# MCU.net
KiCad netlist of a schematic drawn in Altium Designer
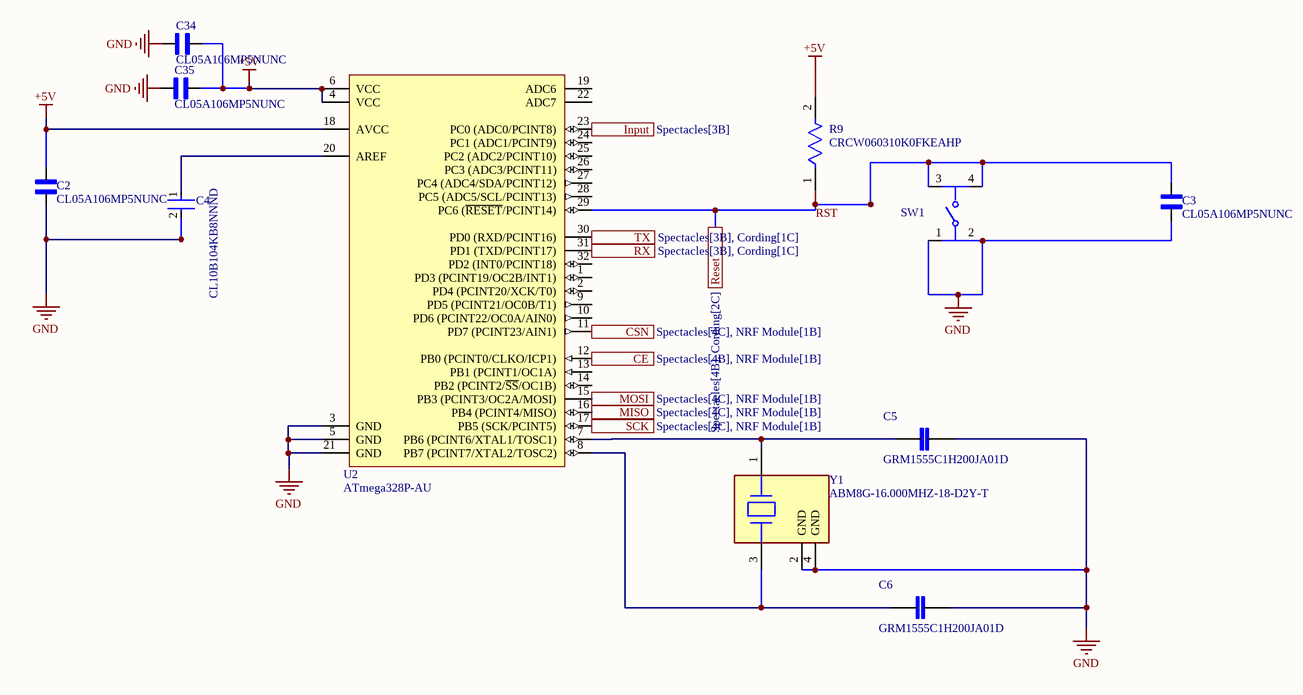
[diagram p0: MCU.SchDoc]

(export (version "E")
  (design (tool "Eeschema 10.0.6"))
  (components
    (comp (ref "C2")
      (value "CL05A106MP5NUNC")
      (footprint "CAPC1005X55N")
      (description "10 ÂµF Â±20% 10V Ceramic Capacitor X5R 0402 (1005 Metric)")
      (fields
        (field (name "OCTOPART") "https://octopart.com/grm188r61a106ke69d-murata-22851381")
        (field (name "MANUFACTURER PART NUMBER") "GRM188R61A106KE69D")
      )
      (libsource (lib "") (part "CL05A106MP5NUNC_1"))
    )
    (comp (ref "C3")
      (value "CL05A106MP5NUNC")
      (footprint "CAPC1005X55N")
      (description "10 ÂµF Â±20% 10V Ceramic Capacitor X5R 0402 (1005 Metric)")
      (fields
        (field (name "OCTOPART") "https://octopart.com/grm188r61a106ke69d-murata-22851381")
        (field (name "MANUFACTURER PART NUMBER") "GRM188R61A106KE69D")
      )
      (libsource (lib "") (part "CL05A106MP5NUNC_1"))
    )
    (comp (ref "C4")
      (value "CL10B104KB8NNND")
      (footprint "FP-CL10-IPC_A")
      (description "Cap Ceramic 100nF 50V X7R ±10% Pad SMD 0603 +125°C T/R")
      (fields (field (name "VOLTAGE") "50V") (field (name "TOLERANCE") "10%"))
      (libsource (lib "Altium Content Vault") (part "b4654b650e69147ec39a6b967a45e02"))
    )
    (comp (ref "C5")
      (value "GRM1555C1H200JA01D")
      (footprint "CAPC1005X55N")
      (description "SMD Capacitor C0G(EIA) with Capacitance: 20pF Tol. 5%. Rated Voltage: 50Vdc")
      (fields (field (name "MF") "Murata"))
      (libsource (lib "GRM1555C1H200JA01D") (part "GRM1555C1H200JA01D"))
    )
    (comp (ref "C6")
      (value "GRM1555C1H200JA01D")
      (footprint "CAPC1005X55N")
      (description "SMD Capacitor C0G(EIA) with Capacitance: 20pF Tol. 5%. Rated Voltage: 50Vdc")
      (fields (field (name "MF") "Murata"))
      (libsource (lib "GRM1555C1H200JA01D") (part "GRM1555C1H200JA01D"))
    )
    (comp (ref "C34")
      (value "CL05A106MP5NUNC")
      (footprint "CAPC1005X55N")
      (description "10 ÂµF Â±20% 10V Ceramic Capacitor X5R 0402 (1005 Metric)")
      (fields
        (field (name "OCTOPART") "https://octopart.com/grm188r61a106ke69d-murata-22851381")
        (field (name "MANUFACTURER PART NUMBER") "GRM188R61A106KE69D")
      )
      (libsource (lib "CL05A106MP5NUNC") (part "CL05A106MP5NUNC"))
    )
    (comp (ref "C35")
      (value "CL05A106MP5NUNC")
      (footprint "CAPC1005X55N")
      (description "10 ÂµF Â±20% 10V Ceramic Capacitor X5R 0402 (1005 Metric)")
      (fields
        (field (name "OCTOPART") "https://octopart.com/grm188r61a106ke69d-murata-22851381")
        (field (name "MANUFACTURER PART NUMBER") "GRM188R61A106KE69D")
      )
      (libsource (lib "CL05A106MP5NUNC") (part "CL05A106MP5NUNC"))
    )
    (comp (ref "R9")
      (value "CRCW060310K0FKEAHP")
      (footprint "FP-CRCW0603-HPe3-MFG")
      (description "RES SMD 10K OHM 1% 1/3W 0603")
      (fields (field (name "TOLERANCE") "1%"))
      (libsource (lib "Altium Content Vault") (part "1029c3af85768c4190bb7ad29bc67b5"))
    )
    (comp (ref "SW1")
      (value "PTS526SK15SMTR2LFS")
      (footprint "FP-PTS526SK15SMTR2LFS-MFG")
      (description "TACT 5.2 X 5.2, 1.5 MM H, 260GF,")
      (fields
        (field (name "MANUFACTURER") "C&K")
        (field (name "OCTOPART") "https://octopart.com/pts526+sk15+smtr2+lfs-c%26k+components-100617999")
      )
      (libsource (lib "Altium Content Vault") (part "b8895f3f4cefb76e1819d2863dba89b"))
    )
    (comp (ref "U2")
      (value "ATmega328P-AU")
      (footprint "32A_M")
      (libsource (lib "Altium Content Vault") (part "MC-8B-ATM48-SQ32"))
    )
    (comp (ref "Y1")
      (value "ABM8G-16.000MHZ-18-D2Y-T")
      (footprint "FP-ABM8G-MFG")
      (description "Crystal 12MHz ±20ppm (Tol) ±30ppm (Stability) 18pF FUND 120Ω 4-Pin SMD T/R")
      (fields (field (name "TOLERANCE") "20ppm"))
      (libsource (lib "Altium Content Vault") (part "48e526d86b7f2615d98721063c72f49"))
    )
  )
  (nets
    (net (code "1") (name "+5V") (class "Default")
      (node (ref "C2") (pin "2") (pinfunction "2_2") (pintype "passive"))
      (node (ref "C34") (pin "1") (pinfunction "1_1") (pintype "passive"))
      (node (ref "C35") (pin "1") (pinfunction "1_1") (pintype "passive"))
      (node (ref "R9") (pin "2") (pinfunction "2_2") (pintype "passive"))
      (node (ref "U2") (pin "18") (pinfunction "AVCC_18") (pintype "power_in"))
      (node (ref "U2") (pin "4") (pinfunction "VCC_4") (pintype "power_in"))
      (node (ref "U2") (pin "6") (pinfunction "VCC_6") (pintype "power_in"))
    )
    (net (code "2") (name "/CE") (class "Default")
      (node (ref "U2") (pin "12") (pinfunction "PB0_(PCINT0/CLKO/ICP1)_12") (pintype "input"))
    )
    (net (code "3") (name "/CSN") (class "Default")
      (node (ref "U2") (pin "11") (pinfunction "PD7_(PCINT23/AIN1)_11") (pintype "output"))
    )
    (net (code "4") (name "/Input") (class "Default")
      (node (ref "U2") (pin "23") (pinfunction "PC0_(ADC0/PCINT8)_23") (pintype "bidirectional"))
    )
    (net (code "5") (name "/MISO") (class "Default")
      (node (ref "U2") (pin "16") (pinfunction "PB4_(PCINT4/MISO)_16") (pintype "bidirectional"))
    )
    (net (code "6") (name "/MOSI") (class "Default")
      (node (ref "U2") (pin "15") (pinfunction "PB3_(PCINT3/OC2A/MOSI)_15") (pintype "passive"))
    )
    (net (code "7") (name "/RST") (class "Default")
      (node (ref "C3") (pin "2") (pinfunction "2_2") (pintype "passive"))
      (node (ref "R9") (pin "1") (pinfunction "1_1") (pintype "passive"))
      (node (ref "SW1") (pin "3") (pinfunction "3_3") (pintype "passive"))
      (node (ref "SW1") (pin "4") (pinfunction "4_4") (pintype "passive"))
      (node (ref "U2") (pin "29") (pinfunction "PC6_(~{RESET}/PCINT14)_29") (pintype "bidirectional"))
    )
    (net (code "8") (name "/RX") (class "Default")
      (node (ref "U2") (pin "31") (pinfunction "PD1_(TXD/PCINT17)_31") (pintype "passive"))
    )
    (net (code "9") (name "/SCK") (class "Default")
      (node (ref "U2") (pin "17") (pinfunction "PB5_(SCK/PCINT5)_17") (pintype "bidirectional"))
    )
    (net (code "10") (name "/TX") (class "Default")
      (node (ref "U2") (pin "30") (pinfunction "PD0_(RXD/PCINT16)_30") (pintype "passive"))
    )
    (net (code "11") (name "GND") (class "Default")
      (node (ref "C2") (pin "1") (pinfunction "1_1") (pintype "passive"))
      (node (ref "C3") (pin "1") (pinfunction "1_1") (pintype "passive"))
      (node (ref "C34") (pin "2") (pinfunction "2_2") (pintype "passive"))
      (node (ref "C35") (pin "2") (pinfunction "2_2") (pintype "passive"))
      (node (ref "C4") (pin "2") (pinfunction "2_2") (pintype "passive"))
      (node (ref "C5") (pin "1") (pinfunction "1_1") (pintype "passive"))
      (node (ref "C6") (pin "1") (pinfunction "1_1") (pintype "passive"))
      (node (ref "SW1") (pin "1") (pinfunction "1_1") (pintype "passive"))
      (node (ref "SW1") (pin "2") (pinfunction "2_2") (pintype "passive"))
      (node (ref "U2") (pin "21") (pinfunction "GND_21") (pintype "power_in"))
      (node (ref "U2") (pin "3") (pinfunction "GND_3") (pintype "power_in"))
      (node (ref "U2") (pin "5") (pinfunction "GND_5") (pintype "power_in"))
      (node (ref "Y1") (pin "2") (pinfunction "GND_2") (pintype "power_in"))
      (node (ref "Y1") (pin "4") (pinfunction "GND_4") (pintype "power_in"))
    )
    (net (code "12") (name "Net-(U2-AREF)") (class "Default")
      (node (ref "C4") (pin "1") (pinfunction "1_1") (pintype "passive"))
      (node (ref "U2") (pin "20") (pinfunction "AREF_20") (pintype "passive"))
    )
    (net (code "13") (name "Net-(U2-PB6_(PCINT6{slash}XTAL1{slash}TOSC1))") (class "Default")
      (node (ref "C5") (pin "2") (pinfunction "2_2") (pintype "passive"))
      (node (ref "U2") (pin "7") (pinfunction "PB6_(PCINT6/XTAL1/TOSC1)_7") (pintype "bidirectional"))
      (node (ref "Y1") (pin "1") (pinfunction "1_1") (pintype "passive"))
    )
    (net (code "14") (name "Net-(U2-PB7_(PCINT7{slash}XTAL2{slash}TOSC2))") (class "Default")
      (node (ref "C6") (pin "2") (pinfunction "2_2") (pintype "passive"))
      (node (ref "U2") (pin "8") (pinfunction "PB7_(PCINT7/XTAL2/TOSC2)_8") (pintype "bidirectional"))
      (node (ref "Y1") (pin "3") (pinfunction "3_3") (pintype "passive"))
    )
    (net (code "15") (name "unconnected-(U2-ADC6-Pad19)") (class "Default")
      (node (ref "U2") (pin "19") (pinfunction "ADC6_19") (pintype "passive"))
    )
    (net (code "16") (name "unconnected-(U2-ADC7-Pad22)") (class "Default")
      (node (ref "U2") (pin "22") (pinfunction "ADC7_22") (pintype "passive"))
    )
    (net (code "17") (name "unconnected-(U2-PB1_(PCINT1{slash}OC1A)-Pad13)") (class "Default")
      (node (ref "U2") (pin "13") (pinfunction "PB1_(PCINT1/OC1A)_13") (pintype "input"))
    )
    (net (code "18") (name "unconnected-(U2-PB2_(PCINT2{slash}~{SS}{slash}OC1B)-Pad14)") (class "Default")
      (node (ref "U2") (pin "14") (pinfunction "PB2_(PCINT2/~{SS}/OC1B)_14") (pintype "bidirectional"))
    )
    (net (code "19") (name "unconnected-(U2-PC1_(ADC1{slash}PCINT9)-Pad24)") (class "Default")
      (node (ref "U2") (pin "24") (pinfunction "PC1_(ADC1/PCINT9)_24") (pintype "bidirectional"))
    )
    (net (code "20") (name "unconnected-(U2-PC2_(ADC2{slash}PCINT10)-Pad25)") (class "Default")
      (node (ref "U2") (pin "25") (pinfunction "PC2_(ADC2/PCINT10)_25") (pintype "bidirectional"))
    )
    (net (code "21") (name "unconnected-(U2-PC3_(ADC3{slash}PCINT11)-Pad26)") (class "Default")
      (node (ref "U2") (pin "26") (pinfunction "PC3_(ADC3/PCINT11)_26") (pintype "bidirectional"))
    )
    (net (code "22") (name "unconnected-(U2-PC4_(ADC4{slash}SDA{slash}PCINT12)-Pad27)") (class "Default")
      (node (ref "U2") (pin "27") (pinfunction "PC4_(ADC4/SDA/PCINT12)_27") (pintype "output"))
    )
    (net (code "23") (name "unconnected-(U2-PC5_(ADC5{slash}SCL{slash}PCINT13)-Pad28)") (class "Default")
      (node (ref "U2") (pin "28") (pinfunction "PC5_(ADC5/SCL/PCINT13)_28") (pintype "output"))
    )
    (net (code "24") (name "unconnected-(U2-PD2_(INT0{slash}PCINT18)-Pad32)") (class "Default")
      (node (ref "U2") (pin "32") (pinfunction "PD2_(INT0/PCINT18)_32") (pintype "bidirectional"))
    )
    (net (code "25") (name "unconnected-(U2-PD3_(PCINT19{slash}OC2B{slash}INT1)-Pad1)") (class "Default")
      (node (ref "U2") (pin "1") (pinfunction "PD3_(PCINT19/OC2B/INT1)_1") (pintype "bidirectional"))
    )
    (net (code "26") (name "unconnected-(U2-PD4_(PCINT20{slash}XCK{slash}T0)-Pad2)") (class "Default")
      (node (ref "U2") (pin "2") (pinfunction "PD4_(PCINT20/XCK/T0)_2") (pintype "bidirectional"))
    )
    (net (code "27") (name "unconnected-(U2-PD5_(PCINT21{slash}OC0B{slash}T1)-Pad9)") (class "Default")
      (node (ref "U2") (pin "9") (pinfunction "PD5_(PCINT21/OC0B/T1)_9") (pintype "output"))
    )
    (net (code "28") (name "unconnected-(U2-PD6_(PCINT22{slash}OC0A{slash}AIN0)-Pad10)") (class "Default")
      (node (ref "U2") (pin "10") (pinfunction "PD6_(PCINT22/OC0A/AIN0)_10") (pintype "output"))
    )
  )
)
